# dac_cape.net
KiCad netlist of a schematic drawn in EAGLE
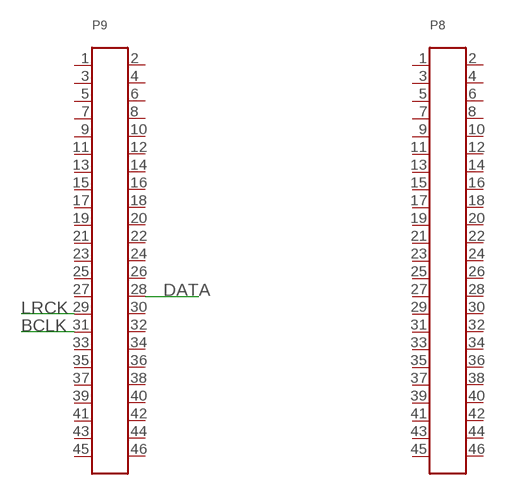
[diagram p0: schematic, sheet 1]
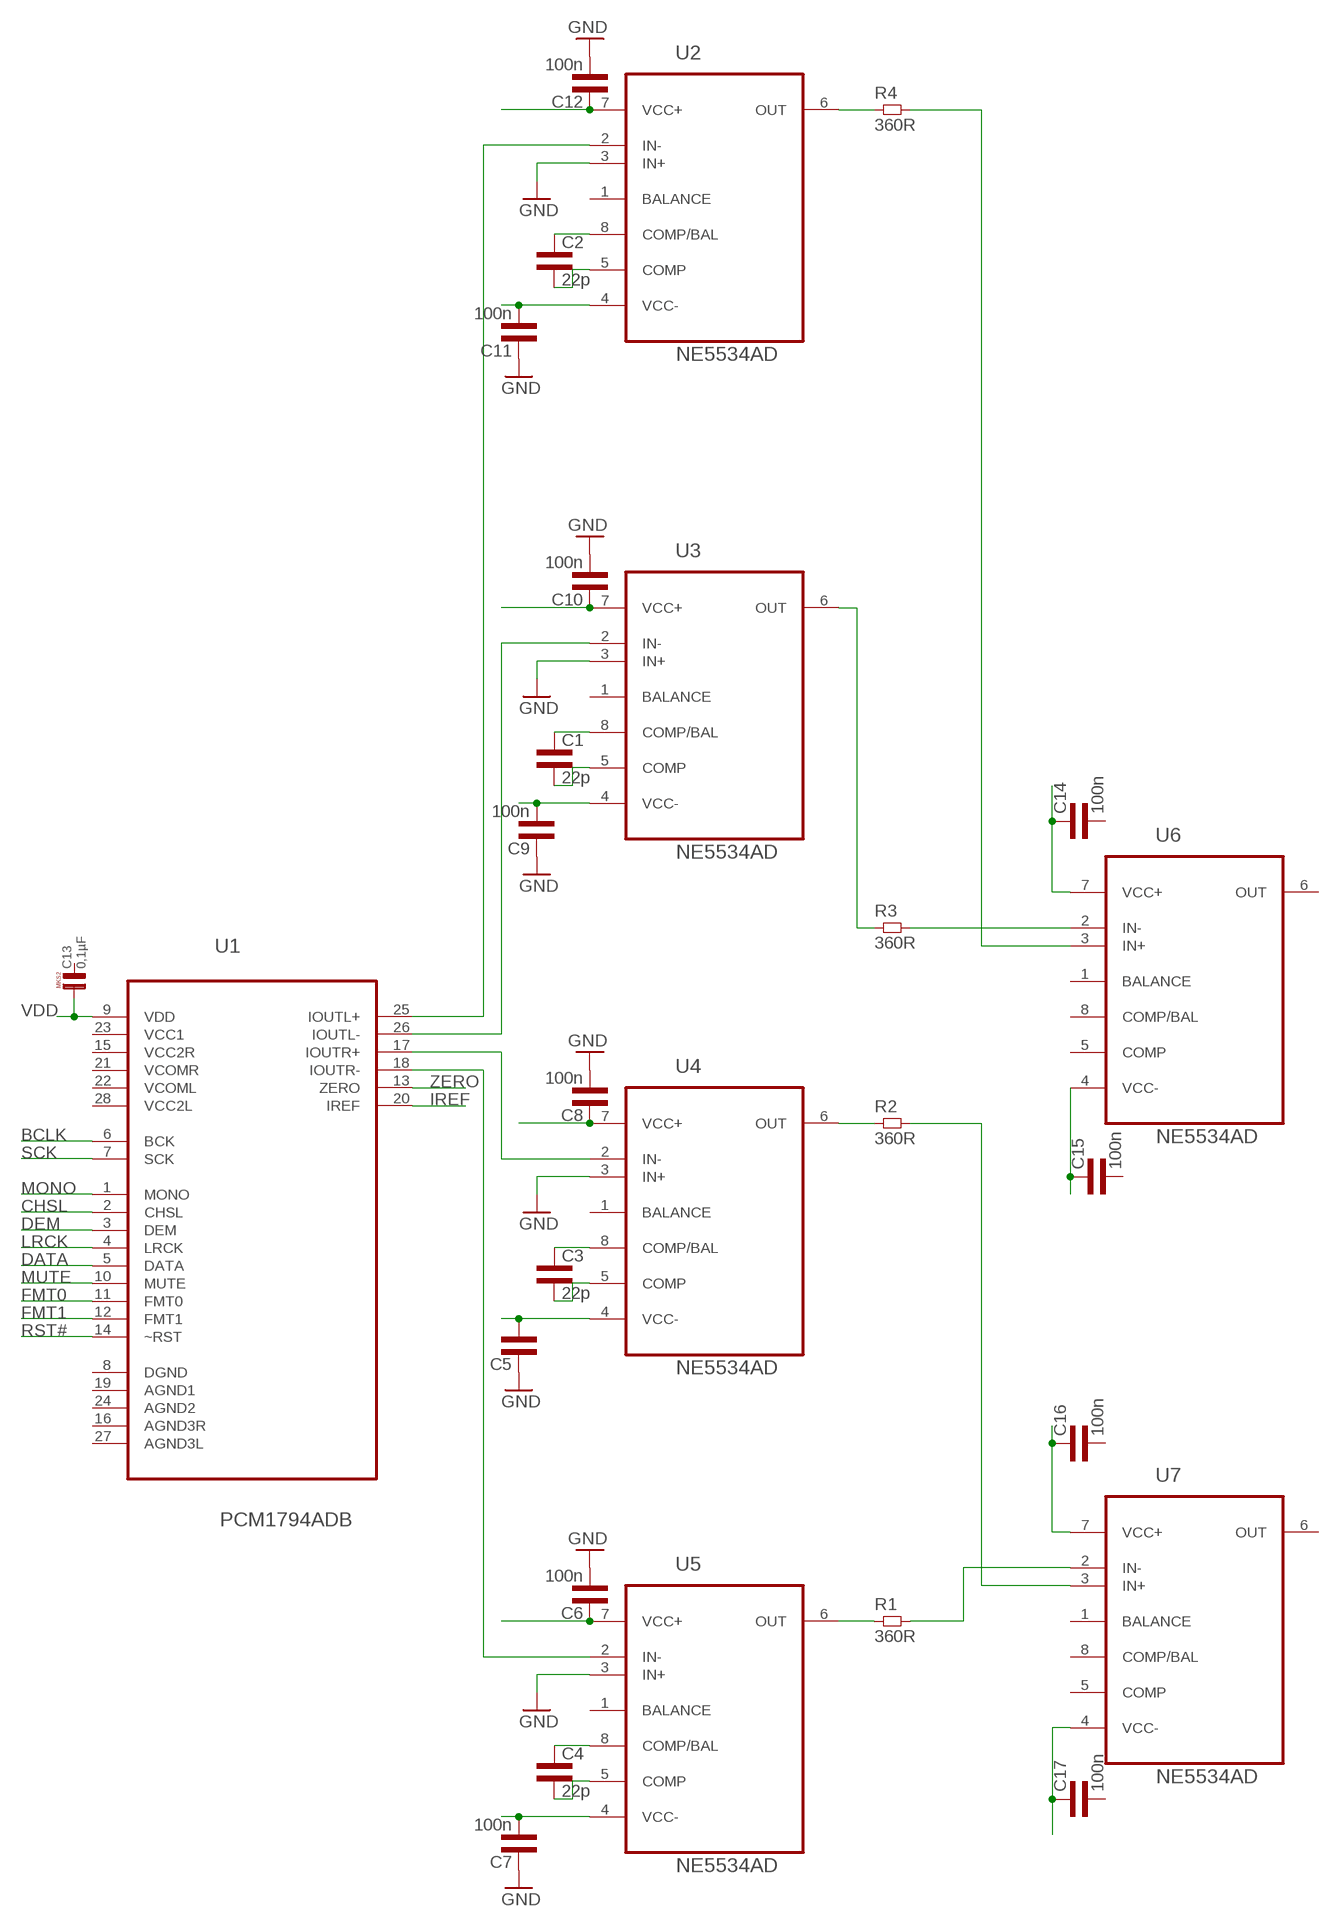
[diagram p1: schematic, sheet 2]

(export (version "E")
  (design (tool "Eeschema 10.0.6"))
  (components
    (comp (ref "C1")
      (value "22p")
      (footprint "eagle-import:0603L3")
      (libsource (lib "eagle-import") (part "CAP0603L3"))
    )
    (comp (ref "C2")
      (value "22p")
      (footprint "eagle-import:0603L3")
      (libsource (lib "eagle-import") (part "CAP0603L3"))
    )
    (comp (ref "C3")
      (value "22p")
      (footprint "eagle-import:0603L3")
      (libsource (lib "eagle-import") (part "CAP0603L3"))
    )
    (comp (ref "C4")
      (value "22p")
      (footprint "eagle-import:0603L3")
      (libsource (lib "eagle-import") (part "CAP0603L3"))
    )
    (comp (ref "C5")
      (value "CAP0603L3")
      (footprint "eagle-import:0603L3")
      (libsource (lib "eagle-import") (part "CAP0603L3"))
    )
    (comp (ref "C6")
      (value "100n")
      (footprint "eagle-import:0603L3")
      (libsource (lib "eagle-import") (part "CAP0603L3"))
    )
    (comp (ref "C7")
      (value "100n")
      (footprint "eagle-import:0603L3")
      (libsource (lib "eagle-import") (part "CAP0603L3"))
    )
    (comp (ref "C8")
      (value "100n")
      (footprint "eagle-import:0603L3")
      (libsource (lib "eagle-import") (part "CAP0603L3"))
    )
    (comp (ref "C9")
      (value "100n")
      (footprint "eagle-import:0603L3")
      (libsource (lib "eagle-import") (part "CAP0603L3"))
    )
    (comp (ref "C10")
      (value "100n")
      (footprint "eagle-import:0603L3")
      (libsource (lib "eagle-import") (part "CAP0603L3"))
    )
    (comp (ref "C11")
      (value "100n")
      (footprint "eagle-import:0603L3")
      (libsource (lib "eagle-import") (part "CAP0603L3"))
    )
    (comp (ref "C12")
      (value "100n")
      (footprint "eagle-import:0603L3")
      (libsource (lib "eagle-import") (part "CAP0603L3"))
    )
    (comp (ref "C13")
      (value "0,1µF")
      (footprint "eagle-import:R5B3")
      (libsource (lib "eagle-import") (part "0,1µF"))
    )
    (comp (ref "C14")
      (value "100n")
      (footprint "eagle-import:0603L3")
      (libsource (lib "eagle-import") (part "CAP0603L3"))
    )
    (comp (ref "C15")
      (value "100n")
      (footprint "eagle-import:0603L3")
      (libsource (lib "eagle-import") (part "CAP0603L3"))
    )
    (comp (ref "C16")
      (value "100n")
      (footprint "eagle-import:0603L3")
      (libsource (lib "eagle-import") (part "CAP0603L3"))
    )
    (comp (ref "C17")
      (value "100n")
      (footprint "eagle-import:0603L3")
      (libsource (lib "eagle-import") (part "CAP0603L3"))
    )
    (comp (ref "R1")
      (value "360R")
      (footprint "eagle-import:0603L3")
      (libsource (lib "eagle-import") (part "RES0603L3"))
    )
    (comp (ref "R2")
      (value "360R")
      (footprint "eagle-import:0603L3")
      (libsource (lib "eagle-import") (part "RES0603L3"))
    )
    (comp (ref "R3")
      (value "360R")
      (footprint "eagle-import:0603L3")
      (libsource (lib "eagle-import") (part "RES0603L3"))
    )
    (comp (ref "R4")
      (value "360R")
      (footprint "eagle-import:0603L3")
      (libsource (lib "eagle-import") (part "RES0603L3"))
    )
    (comp (ref "U1")
      (value "PCM1794ADB")
      (footprint "eagle-import:SOP65P780X200-28N")
      (libsource (lib "eagle-import") (part "PCM1794ADB"))
    )
    (comp (ref "U2")
      (value "NE5534AD")
      (footprint "eagle-import:SOIC127P600X175-8N")
      (libsource (lib "eagle-import") (part "NE5534AD"))
    )
    (comp (ref "U3")
      (value "NE5534AD")
      (footprint "eagle-import:SOIC127P600X175-8N")
      (libsource (lib "eagle-import") (part "NE5534AD"))
    )
    (comp (ref "U4")
      (value "NE5534AD")
      (footprint "eagle-import:SOIC127P600X175-8N")
      (libsource (lib "eagle-import") (part "NE5534AD"))
    )
    (comp (ref "U5")
      (value "NE5534AD")
      (footprint "eagle-import:SOIC127P600X175-8N")
      (libsource (lib "eagle-import") (part "NE5534AD"))
    )
    (comp (ref "U6")
      (value "NE5534AD")
      (footprint "eagle-import:SOIC127P600X175-8N")
      (libsource (lib "eagle-import") (part "NE5534AD"))
    )
    (comp (ref "U7")
      (value "NE5534AD")
      (footprint "eagle-import:SOIC127P600X175-8N")
      (libsource (lib "eagle-import") (part "NE5534AD"))
    )
    (comp (ref "P8")
      (value "PINHD-2X23")
      (footprint "eagle-import:2X23")
      (libsource (lib "eagle-import") (part "PINHD-2X23"))
    )
    (comp (ref "P9")
      (value "PINHD-2X23")
      (footprint "eagle-import:2X23")
      (libsource (lib "eagle-import") (part "PINHD-2X23"))
    )
  )
  (nets
    (net (code "1") (name "BCLK") (class "Default")
      (node (ref "P9") (pin "31") (pinfunction "31_31") (pintype "bidirectional"))
      (node (ref "U1") (pin "6") (pinfunction "BCK_6") (pintype "input"))
    )
    (net (code "2") (name "CHSL") (class "Default")
      (node (ref "U1") (pin "2") (pinfunction "CHSL_2") (pintype "input"))
    )
    (net (code "3") (name "DATA") (class "Default")
      (node (ref "P9") (pin "28") (pinfunction "28_28") (pintype "bidirectional"))
      (node (ref "U1") (pin "5") (pinfunction "DATA_5") (pintype "input"))
    )
    (net (code "4") (name "DEM") (class "Default")
      (node (ref "U1") (pin "3") (pinfunction "DEM_3") (pintype "input"))
    )
    (net (code "5") (name "FMT0") (class "Default")
      (node (ref "U1") (pin "11") (pinfunction "FMT0_11") (pintype "input"))
    )
    (net (code "6") (name "FMT1") (class "Default")
      (node (ref "U1") (pin "12") (pinfunction "FMT1_12") (pintype "input"))
    )
    (net (code "7") (name "GND") (class "Default")
      (node (ref "C10") (pin "P$2") (pinfunction "2_P$2") (pintype "bidirectional"))
      (node (ref "C11") (pin "P$1") (pinfunction "1_P$1") (pintype "bidirectional"))
      (node (ref "C12") (pin "P$2") (pinfunction "2_P$2") (pintype "bidirectional"))
      (node (ref "C5") (pin "P$1") (pinfunction "1_P$1") (pintype "bidirectional"))
      (node (ref "C6") (pin "P$2") (pinfunction "2_P$2") (pintype "bidirectional"))
      (node (ref "C7") (pin "P$1") (pinfunction "1_P$1") (pintype "bidirectional"))
      (node (ref "C8") (pin "P$2") (pinfunction "2_P$2") (pintype "bidirectional"))
      (node (ref "C9") (pin "P$1") (pinfunction "1_P$1") (pintype "bidirectional"))
      (node (ref "U2") (pin "3") (pinfunction "IN+_3") (pintype "input"))
      (node (ref "U3") (pin "3") (pinfunction "IN+_3") (pintype "input"))
      (node (ref "U4") (pin "3") (pinfunction "IN+_3") (pintype "input"))
      (node (ref "U5") (pin "3") (pinfunction "IN+_3") (pintype "input"))
    )
    (net (code "8") (name "IREF") (class "Default")
      (node (ref "U1") (pin "20") (pinfunction "IREF_20") (pintype "output"))
    )
    (net (code "9") (name "LRCK") (class "Default")
      (node (ref "P9") (pin "29") (pinfunction "29_29") (pintype "bidirectional"))
      (node (ref "U1") (pin "4") (pinfunction "LRCK_4") (pintype "input"))
    )
    (net (code "10") (name "MONO") (class "Default")
      (node (ref "U1") (pin "1") (pinfunction "MONO_1") (pintype "input"))
    )
    (net (code "11") (name "MUTE") (class "Default")
      (node (ref "U1") (pin "10") (pinfunction "MUTE_10") (pintype "input"))
    )
    (net (code "12") (name "Net-(C1-1)") (class "Default")
      (node (ref "C1") (pin "P$1") (pinfunction "1_P$1") (pintype "bidirectional"))
      (node (ref "U3") (pin "8") (pinfunction "COMP/BAL_8") (pintype "input"))
    )
    (net (code "13") (name "Net-(C1-2)") (class "Default")
      (node (ref "C1") (pin "P$2") (pinfunction "2_P$2") (pintype "bidirectional"))
      (node (ref "U3") (pin "5") (pinfunction "COMP_5") (pintype "input"))
    )
    (net (code "14") (name "Net-(C2-1)") (class "Default")
      (node (ref "C2") (pin "P$1") (pinfunction "1_P$1") (pintype "bidirectional"))
      (node (ref "U2") (pin "8") (pinfunction "COMP/BAL_8") (pintype "input"))
    )
    (net (code "15") (name "Net-(C2-2)") (class "Default")
      (node (ref "C2") (pin "P$2") (pinfunction "2_P$2") (pintype "bidirectional"))
      (node (ref "U2") (pin "5") (pinfunction "COMP_5") (pintype "input"))
    )
    (net (code "16") (name "Net-(C3-1)") (class "Default")
      (node (ref "C3") (pin "P$1") (pinfunction "1_P$1") (pintype "bidirectional"))
      (node (ref "U4") (pin "8") (pinfunction "COMP/BAL_8") (pintype "input"))
    )
    (net (code "17") (name "Net-(C3-2)") (class "Default")
      (node (ref "C3") (pin "P$2") (pinfunction "2_P$2") (pintype "bidirectional"))
      (node (ref "U4") (pin "5") (pinfunction "COMP_5") (pintype "input"))
    )
    (net (code "18") (name "Net-(C4-1)") (class "Default")
      (node (ref "C4") (pin "P$1") (pinfunction "1_P$1") (pintype "bidirectional"))
      (node (ref "U5") (pin "8") (pinfunction "COMP/BAL_8") (pintype "input"))
    )
    (net (code "19") (name "Net-(C4-2)") (class "Default")
      (node (ref "C4") (pin "P$2") (pinfunction "2_P$2") (pintype "bidirectional"))
      (node (ref "U5") (pin "5") (pinfunction "COMP_5") (pintype "input"))
    )
    (net (code "20") (name "Net-(C5-2)") (class "Default")
      (node (ref "C5") (pin "P$2") (pinfunction "2_P$2") (pintype "bidirectional"))
      (node (ref "U4") (pin "4") (pinfunction "VCC-_4") (pintype "power_in"))
    )
    (net (code "21") (name "Net-(C6-1)") (class "Default")
      (node (ref "C6") (pin "P$1") (pinfunction "1_P$1") (pintype "bidirectional"))
      (node (ref "U5") (pin "7") (pinfunction "VCC+_7") (pintype "power_in"))
    )
    (net (code "22") (name "Net-(C7-2)") (class "Default")
      (node (ref "C7") (pin "P$2") (pinfunction "2_P$2") (pintype "bidirectional"))
      (node (ref "U5") (pin "4") (pinfunction "VCC-_4") (pintype "power_in"))
    )
    (net (code "23") (name "Net-(C8-1)") (class "Default")
      (node (ref "C8") (pin "P$1") (pinfunction "1_P$1") (pintype "bidirectional"))
      (node (ref "U4") (pin "7") (pinfunction "VCC+_7") (pintype "power_in"))
    )
    (net (code "24") (name "Net-(C9-2)") (class "Default")
      (node (ref "C9") (pin "P$2") (pinfunction "2_P$2") (pintype "bidirectional"))
      (node (ref "U3") (pin "4") (pinfunction "VCC-_4") (pintype "power_in"))
    )
    (net (code "25") (name "Net-(C10-1)") (class "Default")
      (node (ref "C10") (pin "P$1") (pinfunction "1_P$1") (pintype "bidirectional"))
      (node (ref "U3") (pin "7") (pinfunction "VCC+_7") (pintype "power_in"))
    )
    (net (code "26") (name "Net-(C11-2)") (class "Default")
      (node (ref "C11") (pin "P$2") (pinfunction "2_P$2") (pintype "bidirectional"))
      (node (ref "U2") (pin "4") (pinfunction "VCC-_4") (pintype "power_in"))
    )
    (net (code "27") (name "Net-(C12-1)") (class "Default")
      (node (ref "C12") (pin "P$1") (pinfunction "1_P$1") (pintype "bidirectional"))
      (node (ref "U2") (pin "7") (pinfunction "VCC+_7") (pintype "power_in"))
    )
    (net (code "28") (name "Net-(C14-1)") (class "Default")
      (node (ref "C14") (pin "P$1") (pinfunction "1_P$1") (pintype "bidirectional"))
      (node (ref "U6") (pin "7") (pinfunction "VCC+_7") (pintype "power_in"))
    )
    (net (code "29") (name "Net-(C15-1)") (class "Default")
      (node (ref "C15") (pin "P$1") (pinfunction "1_P$1") (pintype "bidirectional"))
      (node (ref "U6") (pin "4") (pinfunction "VCC-_4") (pintype "power_in"))
    )
    (net (code "30") (name "Net-(C16-1)") (class "Default")
      (node (ref "C16") (pin "P$1") (pinfunction "1_P$1") (pintype "bidirectional"))
      (node (ref "U7") (pin "7") (pinfunction "VCC+_7") (pintype "power_in"))
    )
    (net (code "31") (name "Net-(C17-1)") (class "Default")
      (node (ref "C17") (pin "P$1") (pinfunction "1_P$1") (pintype "bidirectional"))
      (node (ref "U7") (pin "4") (pinfunction "VCC-_4") (pintype "power_in"))
    )
    (net (code "32") (name "Net-(R1-1)") (class "Default")
      (node (ref "R1") (pin "P$1") (pinfunction "1_P$1") (pintype "bidirectional"))
      (node (ref "U5") (pin "6") (pinfunction "OUT_6") (pintype "output"))
    )
    (net (code "33") (name "Net-(R1-2)") (class "Default")
      (node (ref "R1") (pin "P$2") (pinfunction "2_P$2") (pintype "bidirectional"))
      (node (ref "U7") (pin "2") (pinfunction "IN-_2") (pintype "input"))
    )
    (net (code "34") (name "Net-(R2-1)") (class "Default")
      (node (ref "R2") (pin "P$1") (pinfunction "1_P$1") (pintype "bidirectional"))
      (node (ref "U4") (pin "6") (pinfunction "OUT_6") (pintype "output"))
    )
    (net (code "35") (name "Net-(R2-2)") (class "Default")
      (node (ref "R2") (pin "P$2") (pinfunction "2_P$2") (pintype "bidirectional"))
      (node (ref "U7") (pin "3") (pinfunction "IN+_3") (pintype "input"))
    )
    (net (code "36") (name "Net-(R3-1)") (class "Default")
      (node (ref "R3") (pin "P$1") (pinfunction "1_P$1") (pintype "bidirectional"))
      (node (ref "U3") (pin "6") (pinfunction "OUT_6") (pintype "output"))
    )
    (net (code "37") (name "Net-(R3-2)") (class "Default")
      (node (ref "R3") (pin "P$2") (pinfunction "2_P$2") (pintype "bidirectional"))
      (node (ref "U6") (pin "2") (pinfunction "IN-_2") (pintype "input"))
    )
    (net (code "38") (name "Net-(R4-1)") (class "Default")
      (node (ref "R4") (pin "P$1") (pinfunction "1_P$1") (pintype "bidirectional"))
      (node (ref "U2") (pin "6") (pinfunction "OUT_6") (pintype "output"))
    )
    (net (code "39") (name "Net-(R4-2)") (class "Default")
      (node (ref "R4") (pin "P$2") (pinfunction "2_P$2") (pintype "bidirectional"))
      (node (ref "U6") (pin "3") (pinfunction "IN+_3") (pintype "input"))
    )
    (net (code "40") (name "Net-(U1-IOUTL+)") (class "Default")
      (node (ref "U1") (pin "25") (pinfunction "IOUTL+_25") (pintype "output"))
      (node (ref "U2") (pin "2") (pinfunction "IN-_2") (pintype "input"))
    )
    (net (code "41") (name "Net-(U1-IOUTL-)") (class "Default")
      (node (ref "U1") (pin "26") (pinfunction "IOUTL-_26") (pintype "output"))
      (node (ref "U3") (pin "2") (pinfunction "IN-_2") (pintype "input"))
    )
    (net (code "42") (name "Net-(U1-IOUTR+)") (class "Default")
      (node (ref "U1") (pin "17") (pinfunction "IOUTR+_17") (pintype "output"))
      (node (ref "U4") (pin "2") (pinfunction "IN-_2") (pintype "input"))
    )
    (net (code "43") (name "Net-(U1-IOUTR-)") (class "Default")
      (node (ref "U1") (pin "18") (pinfunction "IOUTR-_18") (pintype "output"))
      (node (ref "U5") (pin "2") (pinfunction "IN-_2") (pintype "input"))
    )
    (net (code "44") (name "RST#") (class "Default")
      (node (ref "U1") (pin "14") (pinfunction "~{RST}_14") (pintype "input"))
    )
    (net (code "45") (name "SCK") (class "Default")
      (node (ref "U1") (pin "7") (pinfunction "SCK_7") (pintype "input"))
    )
    (net (code "46") (name "VCC1") (class "Default")
      (node (ref "U1") (pin "23") (pinfunction "VCC1_23") (pintype "power_in"))
    )
    (net (code "47") (name "VCC2L") (class "Default")
      (node (ref "U1") (pin "28") (pinfunction "VCC2L_28") (pintype "power_in"))
    )
    (net (code "48") (name "VCC2R") (class "Default")
      (node (ref "U1") (pin "15") (pinfunction "VCC2R_15") (pintype "power_in"))
    )
    (net (code "49") (name "VDD") (class "Default")
      (node (ref "C13") (pin "1") (pinfunction "1_1") (pintype "passive"))
      (node (ref "U1") (pin "9") (pinfunction "VDD_9") (pintype "power_in"))
    )
    (net (code "50") (name "ZERO") (class "Default")
      (node (ref "U1") (pin "13") (pinfunction "ZERO_13") (pintype "output"))
    )
    (net (code "51") (name "unconnected-(C13-Pad2)") (class "Default")
      (node (ref "C13") (pin "2") (pinfunction "2_2") (pintype "passive"))
    )
    (net (code "52") (name "unconnected-(C14-2-PadP$2)") (class "Default")
      (node (ref "C14") (pin "P$2") (pinfunction "2_P$2") (pintype "bidirectional"))
    )
    (net (code "53") (name "unconnected-(C15-2-PadP$2)") (class "Default")
      (node (ref "C15") (pin "P$2") (pinfunction "2_P$2") (pintype "bidirectional"))
    )
    (net (code "54") (name "unconnected-(C16-2-PadP$2)") (class "Default")
      (node (ref "C16") (pin "P$2") (pinfunction "2_P$2") (pintype "bidirectional"))
    )
    (net (code "55") (name "unconnected-(C17-2-PadP$2)") (class "Default")
      (node (ref "C17") (pin "P$2") (pinfunction "2_P$2") (pintype "bidirectional"))
    )
    (net (code "56") (name "unconnected-(P8-Pad1)") (class "Default")
      (node (ref "P8") (pin "1") (pinfunction "1_1") (pintype "bidirectional"))
    )
    (net (code "57") (name "unconnected-(P8-Pad2)") (class "Default")
      (node (ref "P8") (pin "2") (pinfunction "2_2") (pintype "bidirectional"))
    )
    (net (code "58") (name "unconnected-(P8-Pad3)") (class "Default")
      (node (ref "P8") (pin "3") (pinfunction "3_3") (pintype "bidirectional"))
    )
    (net (code "59") (name "unconnected-(P8-Pad4)") (class "Default")
      (node (ref "P8") (pin "4") (pinfunction "4_4") (pintype "bidirectional"))
    )
    (net (code "60") (name "unconnected-(P8-Pad5)") (class "Default")
      (node (ref "P8") (pin "5") (pinfunction "5_5") (pintype "bidirectional"))
    )
    (net (code "61") (name "unconnected-(P8-Pad6)") (class "Default")
      (node (ref "P8") (pin "6") (pinfunction "6_6") (pintype "bidirectional"))
    )
    (net (code "62") (name "unconnected-(P8-Pad7)") (class "Default")
      (node (ref "P8") (pin "7") (pinfunction "7_7") (pintype "bidirectional"))
    )
    (net (code "63") (name "unconnected-(P8-Pad8)") (class "Default")
      (node (ref "P8") (pin "8") (pinfunction "8_8") (pintype "bidirectional"))
    )
    (net (code "64") (name "unconnected-(P8-Pad9)") (class "Default")
      (node (ref "P8") (pin "9") (pinfunction "9_9") (pintype "bidirectional"))
    )
    (net (code "65") (name "unconnected-(P8-Pad10)") (class "Default")
      (node (ref "P8") (pin "10") (pinfunction "10_10") (pintype "bidirectional"))
    )
    (net (code "66") (name "unconnected-(P8-Pad11)") (class "Default")
      (node (ref "P8") (pin "11") (pinfunction "11_11") (pintype "bidirectional"))
    )
    (net (code "67") (name "unconnected-(P8-Pad12)") (class "Default")
      (node (ref "P8") (pin "12") (pinfunction "12_12") (pintype "bidirectional"))
    )
    (net (code "68") (name "unconnected-(P8-Pad13)") (class "Default")
      (node (ref "P8") (pin "13") (pinfunction "13_13") (pintype "bidirectional"))
    )
    (net (code "69") (name "unconnected-(P8-Pad14)") (class "Default")
      (node (ref "P8") (pin "14") (pinfunction "14_14") (pintype "bidirectional"))
    )
    (net (code "70") (name "unconnected-(P8-Pad15)") (class "Default")
      (node (ref "P8") (pin "15") (pinfunction "15_15") (pintype "bidirectional"))
    )
    (net (code "71") (name "unconnected-(P8-Pad16)") (class "Default")
      (node (ref "P8") (pin "16") (pinfunction "16_16") (pintype "bidirectional"))
    )
    (net (code "72") (name "unconnected-(P8-Pad17)") (class "Default")
      (node (ref "P8") (pin "17") (pinfunction "17_17") (pintype "bidirectional"))
    )
    (net (code "73") (name "unconnected-(P8-Pad18)") (class "Default")
      (node (ref "P8") (pin "18") (pinfunction "18_18") (pintype "bidirectional"))
    )
    (net (code "74") (name "unconnected-(P8-Pad19)") (class "Default")
      (node (ref "P8") (pin "19") (pinfunction "19_19") (pintype "bidirectional"))
    )
    (net (code "75") (name "unconnected-(P8-Pad20)") (class "Default")
      (node (ref "P8") (pin "20") (pinfunction "20_20") (pintype "bidirectional"))
    )
    (net (code "76") (name "unconnected-(P8-Pad21)") (class "Default")
      (node (ref "P8") (pin "21") (pinfunction "21_21") (pintype "bidirectional"))
    )
    (net (code "77") (name "unconnected-(P8-Pad22)") (class "Default")
      (node (ref "P8") (pin "22") (pinfunction "22_22") (pintype "bidirectional"))
    )
    (net (code "78") (name "unconnected-(P8-Pad23)") (class "Default")
      (node (ref "P8") (pin "23") (pinfunction "23_23") (pintype "bidirectional"))
    )
    (net (code "79") (name "unconnected-(P8-Pad24)") (class "Default")
      (node (ref "P8") (pin "24") (pinfunction "24_24") (pintype "bidirectional"))
    )
    (net (code "80") (name "unconnected-(P8-Pad25)") (class "Default")
      (node (ref "P8") (pin "25") (pinfunction "25_25") (pintype "bidirectional"))
    )
    (net (code "81") (name "unconnected-(P8-Pad26)") (class "Default")
      (node (ref "P8") (pin "26") (pinfunction "26_26") (pintype "bidirectional"))
    )
    (net (code "82") (name "unconnected-(P8-Pad27)") (class "Default")
      (node (ref "P8") (pin "27") (pinfunction "27_27") (pintype "bidirectional"))
    )
    (net (code "83") (name "unconnected-(P8-Pad28)") (class "Default")
      (node (ref "P8") (pin "28") (pinfunction "28_28") (pintype "bidirectional"))
    )
    (net (code "84") (name "unconnected-(P8-Pad29)") (class "Default")
      (node (ref "P8") (pin "29") (pinfunction "29_29") (pintype "bidirectional"))
    )
    (net (code "85") (name "unconnected-(P8-Pad30)") (class "Default")
      (node (ref "P8") (pin "30") (pinfunction "30_30") (pintype "bidirectional"))
    )
    (net (code "86") (name "unconnected-(P8-Pad31)") (class "Default")
      (node (ref "P8") (pin "31") (pinfunction "31_31") (pintype "bidirectional"))
    )
    (net (code "87") (name "unconnected-(P8-Pad32)") (class "Default")
      (node (ref "P8") (pin "32") (pinfunction "32_32") (pintype "bidirectional"))
    )
    (net (code "88") (name "unconnected-(P8-Pad33)") (class "Default")
      (node (ref "P8") (pin "33") (pinfunction "33_33") (pintype "bidirectional"))
    )
    (net (code "89") (name "unconnected-(P8-Pad34)") (class "Default")
      (node (ref "P8") (pin "34") (pinfunction "34_34") (pintype "bidirectional"))
    )
    (net (code "90") (name "unconnected-(P8-Pad35)") (class "Default")
      (node (ref "P8") (pin "35") (pinfunction "35_35") (pintype "bidirectional"))
    )
    (net (code "91") (name "unconnected-(P8-Pad36)") (class "Default")
      (node (ref "P8") (pin "36") (pinfunction "36_36") (pintype "bidirectional"))
    )
    (net (code "92") (name "unconnected-(P8-Pad37)") (class "Default")
      (node (ref "P8") (pin "37") (pinfunction "37_37") (pintype "bidirectional"))
    )
    (net (code "93") (name "unconnected-(P8-Pad38)") (class "Default")
      (node (ref "P8") (pin "38") (pinfunction "38_38") (pintype "bidirectional"))
    )
    (net (code "94") (name "unconnected-(P8-Pad39)") (class "Default")
      (node (ref "P8") (pin "39") (pinfunction "39_39") (pintype "bidirectional"))
    )
    (net (code "95") (name "unconnected-(P8-Pad40)") (class "Default")
      (node (ref "P8") (pin "40") (pinfunction "40_40") (pintype "bidirectional"))
    )
    (net (code "96") (name "unconnected-(P8-Pad41)") (class "Default")
      (node (ref "P8") (pin "41") (pinfunction "41_41") (pintype "bidirectional"))
    )
    (net (code "97") (name "unconnected-(P8-Pad42)") (class "Default")
      (node (ref "P8") (pin "42") (pinfunction "42_42") (pintype "bidirectional"))
    )
    (net (code "98") (name "unconnected-(P8-Pad43)") (class "Default")
      (node (ref "P8") (pin "43") (pinfunction "43_43") (pintype "bidirectional"))
    )
    (net (code "99") (name "unconnected-(P8-Pad44)") (class "Default")
      (node (ref "P8") (pin "44") (pinfunction "44_44") (pintype "bidirectional"))
    )
    (net (code "100") (name "unconnected-(P8-Pad45)") (class "Default")
      (node (ref "P8") (pin "45") (pinfunction "45_45") (pintype "bidirectional"))
    )
    (net (code "101") (name "unconnected-(P8-Pad46)") (class "Default")
      (node (ref "P8") (pin "46") (pinfunction "46_46") (pintype "bidirectional"))
    )
    (net (code "102") (name "unconnected-(P9-Pad1)") (class "Default")
      (node (ref "P9") (pin "1") (pinfunction "1_1") (pintype "bidirectional"))
    )
    (net (code "103") (name "unconnected-(P9-Pad2)") (class "Default")
      (node (ref "P9") (pin "2") (pinfunction "2_2") (pintype "bidirectional"))
    )
    (net (code "104") (name "unconnected-(P9-Pad3)") (class "Default")
      (node (ref "P9") (pin "3") (pinfunction "3_3") (pintype "bidirectional"))
    )
    (net (code "105") (name "unconnected-(P9-Pad4)") (class "Default")
      (node (ref "P9") (pin "4") (pinfunction "4_4") (pintype "bidirectional"))
    )
    (net (code "106") (name "unconnected-(P9-Pad5)") (class "Default")
      (node (ref "P9") (pin "5") (pinfunction "5_5") (pintype "bidirectional"))
    )
    (net (code "107") (name "unconnected-(P9-Pad6)") (class "Default")
      (node (ref "P9") (pin "6") (pinfunction "6_6") (pintype "bidirectional"))
    )
    (net (code "108") (name "unconnected-(P9-Pad7)") (class "Default")
      (node (ref "P9") (pin "7") (pinfunction "7_7") (pintype "bidirectional"))
    )
    (net (code "109") (name "unconnected-(P9-Pad8)") (class "Default")
      (node (ref "P9") (pin "8") (pinfunction "8_8") (pintype "bidirectional"))
    )
    (net (code "110") (name "unconnected-(P9-Pad9)") (class "Default")
      (node (ref "P9") (pin "9") (pinfunction "9_9") (pintype "bidirectional"))
    )
    (net (code "111") (name "unconnected-(P9-Pad10)") (class "Default")
      (node (ref "P9") (pin "10") (pinfunction "10_10") (pintype "bidirectional"))
    )
    (net (code "112") (name "unconnected-(P9-Pad11)") (class "Default")
      (node (ref "P9") (pin "11") (pinfunction "11_11") (pintype "bidirectional"))
    )
    (net (code "113") (name "unconnected-(P9-Pad12)") (class "Default")
      (node (ref "P9") (pin "12") (pinfunction "12_12") (pintype "bidirectional"))
    )
    (net (code "114") (name "unconnected-(P9-Pad13)") (class "Default")
      (node (ref "P9") (pin "13") (pinfunction "13_13") (pintype "bidirectional"))
    )
    (net (code "115") (name "unconnected-(P9-Pad14)") (class "Default")
      (node (ref "P9") (pin "14") (pinfunction "14_14") (pintype "bidirectional"))
    )
    (net (code "116") (name "unconnected-(P9-Pad15)") (class "Default")
      (node (ref "P9") (pin "15") (pinfunction "15_15") (pintype "bidirectional"))
    )
    (net (code "117") (name "unconnected-(P9-Pad16)") (class "Default")
      (node (ref "P9") (pin "16") (pinfunction "16_16") (pintype "bidirectional"))
    )
    (net (code "118") (name "unconnected-(P9-Pad17)") (class "Default")
      (node (ref "P9") (pin "17") (pinfunction "17_17") (pintype "bidirectional"))
    )
    (net (code "119") (name "unconnected-(P9-Pad18)") (class "Default")
      (node (ref "P9") (pin "18") (pinfunction "18_18") (pintype "bidirectional"))
    )
    (net (code "120") (name "unconnected-(P9-Pad19)") (class "Default")
      (node (ref "P9") (pin "19") (pinfunction "19_19") (pintype "bidirectional"))
    )
    (net (code "121") (name "unconnected-(P9-Pad20)") (class "Default")
      (node (ref "P9") (pin "20") (pinfunction "20_20") (pintype "bidirectional"))
    )
    (net (code "122") (name "unconnected-(P9-Pad21)") (class "Default")
      (node (ref "P9") (pin "21") (pinfunction "21_21") (pintype "bidirectional"))
    )
    (net (code "123") (name "unconnected-(P9-Pad22)") (class "Default")
      (node (ref "P9") (pin "22") (pinfunction "22_22") (pintype "bidirectional"))
    )
    (net (code "124") (name "unconnected-(P9-Pad23)") (class "Default")
      (node (ref "P9") (pin "23") (pinfunction "23_23") (pintype "bidirectional"))
    )
    (net (code "125") (name "unconnected-(P9-Pad24)") (class "Default")
      (node (ref "P9") (pin "24") (pinfunction "24_24") (pintype "bidirectional"))
    )
    (net (code "126") (name "unconnected-(P9-Pad25)") (class "Default")
      (node (ref "P9") (pin "25") (pinfunction "25_25") (pintype "bidirectional"))
    )
    (net (code "127") (name "unconnected-(P9-Pad26)") (class "Default")
      (node (ref "P9") (pin "26") (pinfunction "26_26") (pintype "bidirectional"))
    )
    (net (code "128") (name "unconnected-(P9-Pad27)") (class "Default")
      (node (ref "P9") (pin "27") (pinfunction "27_27") (pintype "bidirectional"))
    )
    (net (code "129") (name "unconnected-(P9-Pad30)") (class "Default")
      (node (ref "P9") (pin "30") (pinfunction "30_30") (pintype "bidirectional"))
    )
    (net (code "130") (name "unconnected-(P9-Pad32)") (class "Default")
      (node (ref "P9") (pin "32") (pinfunction "32_32") (pintype "bidirectional"))
    )
    (net (code "131") (name "unconnected-(P9-Pad33)") (class "Default")
      (node (ref "P9") (pin "33") (pinfunction "33_33") (pintype "bidirectional"))
    )
    (net (code "132") (name "unconnected-(P9-Pad34)") (class "Default")
      (node (ref "P9") (pin "34") (pinfunction "34_34") (pintype "bidirectional"))
    )
    (net (code "133") (name "unconnected-(P9-Pad35)") (class "Default")
      (node (ref "P9") (pin "35") (pinfunction "35_35") (pintype "bidirectional"))
    )
    (net (code "134") (name "unconnected-(P9-Pad36)") (class "Default")
      (node (ref "P9") (pin "36") (pinfunction "36_36") (pintype "bidirectional"))
    )
    (net (code "135") (name "unconnected-(P9-Pad37)") (class "Default")
      (node (ref "P9") (pin "37") (pinfunction "37_37") (pintype "bidirectional"))
    )
    (net (code "136") (name "unconnected-(P9-Pad38)") (class "Default")
      (node (ref "P9") (pin "38") (pinfunction "38_38") (pintype "bidirectional"))
    )
    (net (code "137") (name "unconnected-(P9-Pad39)") (class "Default")
      (node (ref "P9") (pin "39") (pinfunction "39_39") (pintype "bidirectional"))
    )
    (net (code "138") (name "unconnected-(P9-Pad40)") (class "Default")
      (node (ref "P9") (pin "40") (pinfunction "40_40") (pintype "bidirectional"))
    )
    (net (code "139") (name "unconnected-(P9-Pad41)") (class "Default")
      (node (ref "P9") (pin "41") (pinfunction "41_41") (pintype "bidirectional"))
    )
    (net (code "140") (name "unconnected-(P9-Pad42)") (class "Default")
      (node (ref "P9") (pin "42") (pinfunction "42_42") (pintype "bidirectional"))
    )
    (net (code "141") (name "unconnected-(P9-Pad43)") (class "Default")
      (node (ref "P9") (pin "43") (pinfunction "43_43") (pintype "bidirectional"))
    )
    (net (code "142") (name "unconnected-(P9-Pad44)") (class "Default")
      (node (ref "P9") (pin "44") (pinfunction "44_44") (pintype "bidirectional"))
    )
    (net (code "143") (name "unconnected-(P9-Pad45)") (class "Default")
      (node (ref "P9") (pin "45") (pinfunction "45_45") (pintype "bidirectional"))
    )
    (net (code "144") (name "unconnected-(P9-Pad46)") (class "Default")
      (node (ref "P9") (pin "46") (pinfunction "46_46") (pintype "bidirectional"))
    )
    (net (code "145") (name "unconnected-(U1-AGND1-Pad19)") (class "Default")
      (node (ref "U1") (pin "19") (pinfunction "AGND1_19") (pintype "passive"))
    )
    (net (code "146") (name "unconnected-(U1-AGND2-Pad24)") (class "Default")
      (node (ref "U1") (pin "24") (pinfunction "AGND2_24") (pintype "passive"))
    )
    (net (code "147") (name "unconnected-(U1-AGND3L-Pad27)") (class "Default")
      (node (ref "U1") (pin "27") (pinfunction "AGND3L_27") (pintype "passive"))
    )
    (net (code "148") (name "unconnected-(U1-AGND3R-Pad16)") (class "Default")
      (node (ref "U1") (pin "16") (pinfunction "AGND3R_16") (pintype "passive"))
    )
    (net (code "149") (name "unconnected-(U1-DGND-Pad8)") (class "Default")
      (node (ref "U1") (pin "8") (pinfunction "DGND_8") (pintype "passive"))
    )
    (net (code "150") (name "unconnected-(U1-VCOML-Pad22)") (class "Default")
      (node (ref "U1") (pin "22") (pinfunction "VCOML_22") (pintype "input"))
    )
    (net (code "151") (name "unconnected-(U1-VCOMR-Pad21)") (class "Default")
      (node (ref "U1") (pin "21") (pinfunction "VCOMR_21") (pintype "input"))
    )
    (net (code "152") (name "unconnected-(U2-BALANCE-Pad1)") (class "Default")
      (node (ref "U2") (pin "1") (pinfunction "BALANCE_1") (pintype "input"))
    )
    (net (code "153") (name "unconnected-(U3-BALANCE-Pad1)") (class "Default")
      (node (ref "U3") (pin "1") (pinfunction "BALANCE_1") (pintype "input"))
    )
    (net (code "154") (name "unconnected-(U4-BALANCE-Pad1)") (class "Default")
      (node (ref "U4") (pin "1") (pinfunction "BALANCE_1") (pintype "input"))
    )
    (net (code "155") (name "unconnected-(U5-BALANCE-Pad1)") (class "Default")
      (node (ref "U5") (pin "1") (pinfunction "BALANCE_1") (pintype "input"))
    )
    (net (code "156") (name "unconnected-(U6-BALANCE-Pad1)") (class "Default")
      (node (ref "U6") (pin "1") (pinfunction "BALANCE_1") (pintype "input"))
    )
    (net (code "157") (name "unconnected-(U6-COMP-Pad5)") (class "Default")
      (node (ref "U6") (pin "5") (pinfunction "COMP_5") (pintype "input"))
    )
    (net (code "158") (name "unconnected-(U6-COMP{slash}BAL-Pad8)") (class "Default")
      (node (ref "U6") (pin "8") (pinfunction "COMP/BAL_8") (pintype "input"))
    )
    (net (code "159") (name "unconnected-(U6-OUT-Pad6)") (class "Default")
      (node (ref "U6") (pin "6") (pinfunction "OUT_6") (pintype "output"))
    )
    (net (code "160") (name "unconnected-(U7-BALANCE-Pad1)") (class "Default")
      (node (ref "U7") (pin "1") (pinfunction "BALANCE_1") (pintype "input"))
    )
    (net (code "161") (name "unconnected-(U7-COMP-Pad5)") (class "Default")
      (node (ref "U7") (pin "5") (pinfunction "COMP_5") (pintype "input"))
    )
    (net (code "162") (name "unconnected-(U7-COMP{slash}BAL-Pad8)") (class "Default")
      (node (ref "U7") (pin "8") (pinfunction "COMP/BAL_8") (pintype "input"))
    )
    (net (code "163") (name "unconnected-(U7-OUT-Pad6)") (class "Default")
      (node (ref "U7") (pin "6") (pinfunction "OUT_6") (pintype "output"))
    )
  )
)
